# AEBS_component_FrontV1_2.net
KiCad netlist of a schematic drawn in Altium Designer
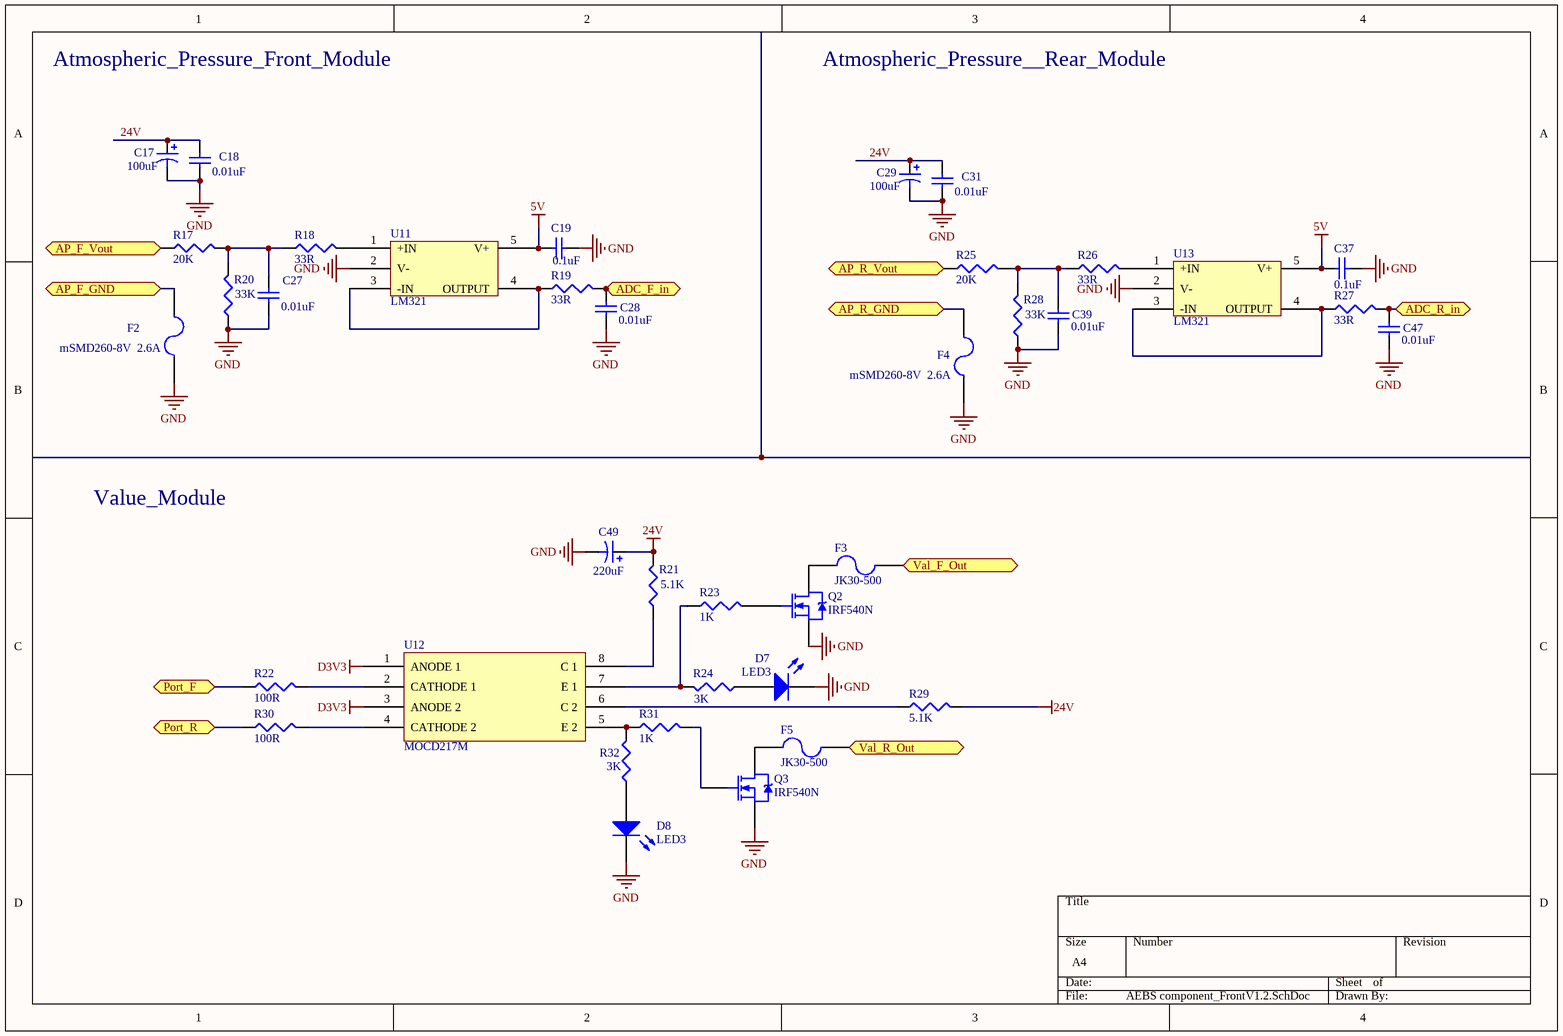
[diagram p0: AEBS component_FrontV1.2.SchDoc]

(export (version "E")
  (design (tool "Eeschema 10.0.6"))
  (components
    (comp (ref "C17")
      (value "100uF")
      (footprint "hg:CAP_POL_10*10.5")
      (description "Polarized Capacitor (Surface Mount)")
      (fields (field (name "PUBLISHER") "Altium Limited"))
      (libsource (lib "Miscellaneous Devices") (part "Cap Pol3"))
    )
    (comp (ref "C18")
      (value "0.01uF")
      (footprint "hg:0805")
      (description "Capacitor (Semiconductor SIM Model)")
      (fields (field (name "PUBLISHER") "Altium Limited"))
      (libsource (lib "Miscellaneous Devices") (part "Cap Semi"))
    )
    (comp (ref "C19")
      (value "0.1uF")
      (footprint "1608[0603]")
      (description "Capacitor (Semiconductor SIM Model)")
      (fields (field (name "PUBLISHER") "Altium Limited"))
      (libsource (lib "Miscellaneous Devices") (part "Cap Semi"))
    )
    (comp (ref "C27")
      (value "0.01uF")
      (footprint "1608[0603]")
      (description "Capacitor (Semiconductor SIM Model)")
      (fields (field (name "PUBLISHER") "Altium Limited"))
      (libsource (lib "Miscellaneous Devices") (part "Cap Semi"))
    )
    (comp (ref "C28")
      (value "0.01uF")
      (footprint "1608[0603]")
      (description "Capacitor (Semiconductor SIM Model)")
      (fields (field (name "PUBLISHER") "Altium Limited"))
      (libsource (lib "Miscellaneous Devices") (part "Cap Semi"))
    )
    (comp (ref "C29")
      (value "100uF")
      (footprint "hg:CAP_POL_10*10.5")
      (description "Polarized Capacitor (Surface Mount)")
      (fields (field (name "PUBLISHER") "Altium Limited"))
      (libsource (lib "Miscellaneous Devices") (part "Cap Pol3"))
    )
    (comp (ref "C31")
      (value "0.01uF")
      (footprint "hg:0805")
      (description "Capacitor (Semiconductor SIM Model)")
      (fields (field (name "PUBLISHER") "Altium Limited"))
      (libsource (lib "Miscellaneous Devices") (part "Cap Semi"))
    )
    (comp (ref "C37")
      (value "0.1uF")
      (footprint "1608[0603]")
      (description "Capacitor (Semiconductor SIM Model)")
      (fields (field (name "PUBLISHER") "Altium Limited"))
      (libsource (lib "Miscellaneous Devices") (part "Cap Semi"))
    )
    (comp (ref "C39")
      (value "0.01uF")
      (footprint "1608[0603]")
      (description "Capacitor (Semiconductor SIM Model)")
      (fields (field (name "PUBLISHER") "Altium Limited"))
      (libsource (lib "Miscellaneous Devices") (part "Cap Semi"))
    )
    (comp (ref "C47")
      (value "0.01uF")
      (footprint "1608[0603]")
      (description "Capacitor (Semiconductor SIM Model)")
      (fields (field (name "PUBLISHER") "Altium Limited"))
      (libsource (lib "Miscellaneous Devices") (part "Cap Semi"))
    )
    (comp (ref "C49")
      (value "220uF")
      (footprint "hg:CAP_POL_12.5*13.5")
      (description "Polarized Capacitor (Radial)")
      (fields (field (name "PUBLISHER") "Altium Limited"))
      (libsource (lib "Miscellaneous Devices") (part "Cap Pol1"))
    )
    (comp (ref "D7")
      (value "LED3")
      (footprint "hg:1206")
      (description "Typical BLUE SiC LED")
      (fields (field (name "PUBLISHER") "Altium Limited"))
      (libsource (lib "Miscellaneous Devices") (part "LED3"))
    )
    (comp (ref "D8")
      (value "LED3")
      (footprint "hg:1206")
      (description "Typical BLUE SiC LED")
      (fields (field (name "PUBLISHER") "Altium Limited"))
      (libsource (lib "Miscellaneous Devices") (part "LED3"))
    )
    (comp (ref "F2")
      (value "mSMD260-8V  2.6A")
      (footprint "1812")
      (description "Fuse")
      (fields (field (name "PUBLISHER") "Altium Limited"))
      (libsource (lib "Miscellaneous Devices") (part "Fuse 2"))
    )
    (comp (ref "F3")
      (value "JK30-500")
      (footprint "hg:JK30-500")
      (description "Fuse")
      (fields (field (name "PUBLISHER") "Altium Limited"))
      (libsource (lib "Miscellaneous Devices") (part "Fuse 2"))
    )
    (comp (ref "F4")
      (value "mSMD260-8V  2.6A")
      (footprint "1812")
      (description "Fuse")
      (fields (field (name "PUBLISHER") "Altium Limited"))
      (libsource (lib "Miscellaneous Devices") (part "Fuse 2"))
    )
    (comp (ref "F5")
      (value "JK30-500")
      (footprint "hg:JK30-500")
      (description "Fuse")
      (fields (field (name "PUBLISHER") "Altium Limited"))
      (libsource (lib "Miscellaneous Devices") (part "Fuse 2"))
    )
    (comp (ref "Q2")
      (value "IRF540N")
      (footprint "TO-220AB")
      (description "N-Channel Power MOSFET")
      (fields (field (name "PUBLISHER") "Altium Limited"))
      (libsource (lib "Miscellaneous Devices") (part "NMOS-2"))
    )
    (comp (ref "Q3")
      (value "IRF540N")
      (footprint "TO-220AB")
      (description "N-Channel Power MOSFET")
      (fields (field (name "PUBLISHER") "Altium Limited"))
      (libsource (lib "Miscellaneous Devices") (part "NMOS-2"))
    )
    (comp (ref "R17")
      (value "20K")
      (footprint "J1-0603")
      (description "Resistor")
      (fields (field (name "PUBLISHER") "Altium Limited"))
      (libsource (lib "Miscellaneous Devices") (part "Res3"))
    )
    (comp (ref "R18")
      (value "33R")
      (footprint "J1-0603")
      (description "Resistor")
      (fields (field (name "PUBLISHER") "Altium Limited"))
      (libsource (lib "Miscellaneous Devices") (part "Res3"))
    )
    (comp (ref "R19")
      (value "33R")
      (footprint "J1-0603")
      (description "Resistor")
      (fields (field (name "PUBLISHER") "Altium Limited"))
      (libsource (lib "Miscellaneous Devices") (part "Res3"))
    )
    (comp (ref "R20")
      (value "33K")
      (footprint "J1-0603")
      (description "Resistor")
      (fields (field (name "PUBLISHER") "Altium Limited"))
      (libsource (lib "Miscellaneous Devices") (part "Res3"))
    )
    (comp (ref "R21")
      (value "5.1K")
      (footprint "J1-0603")
      (description "Resistor")
      (fields (field (name "PUBLISHER") "Altium Limited"))
      (libsource (lib "Miscellaneous Devices") (part "Res3"))
    )
    (comp (ref "R22")
      (value "100R")
      (footprint "J1-0603")
      (description "Resistor")
      (fields (field (name "PUBLISHER") "Altium Limited"))
      (libsource (lib "Miscellaneous Devices") (part "Res3"))
    )
    (comp (ref "R23")
      (value "1K")
      (footprint "J1-0603")
      (description "Resistor")
      (fields (field (name "PUBLISHER") "Altium Limited"))
      (libsource (lib "Miscellaneous Devices") (part "Res3"))
    )
    (comp (ref "R24")
      (value "3K")
      (footprint "J1-0603")
      (description "Resistor")
      (fields (field (name "PUBLISHER") "Altium Limited"))
      (libsource (lib "Miscellaneous Devices") (part "Res3"))
    )
    (comp (ref "R25")
      (value "20K")
      (footprint "J1-0603")
      (description "Resistor")
      (fields (field (name "PUBLISHER") "Altium Limited"))
      (libsource (lib "Miscellaneous Devices") (part "Res3"))
    )
    (comp (ref "R26")
      (value "33R")
      (footprint "J1-0603")
      (description "Resistor")
      (fields (field (name "PUBLISHER") "Altium Limited"))
      (libsource (lib "Miscellaneous Devices") (part "Res3"))
    )
    (comp (ref "R27")
      (value "33R")
      (footprint "J1-0603")
      (description "Resistor")
      (fields (field (name "PUBLISHER") "Altium Limited"))
      (libsource (lib "Miscellaneous Devices") (part "Res3"))
    )
    (comp (ref "R28")
      (value "33K")
      (footprint "J1-0603")
      (description "Resistor")
      (fields (field (name "PUBLISHER") "Altium Limited"))
      (libsource (lib "Miscellaneous Devices") (part "Res3"))
    )
    (comp (ref "R29")
      (value "5.1K")
      (footprint "J1-0603")
      (description "Resistor")
      (fields (field (name "PUBLISHER") "Altium Limited"))
      (libsource (lib "Miscellaneous Devices") (part "Res3"))
    )
    (comp (ref "R30")
      (value "100R")
      (footprint "J1-0603")
      (description "Resistor")
      (fields (field (name "PUBLISHER") "Altium Limited"))
      (libsource (lib "Miscellaneous Devices") (part "Res3"))
    )
    (comp (ref "R31")
      (value "1K")
      (footprint "J1-0603")
      (description "Resistor")
      (fields (field (name "PUBLISHER") "Altium Limited"))
      (libsource (lib "Miscellaneous Devices") (part "Res3"))
    )
    (comp (ref "R32")
      (value "3K")
      (footprint "J1-0603")
      (description "Resistor")
      (fields (field (name "PUBLISHER") "Altium Limited"))
      (libsource (lib "Miscellaneous Devices") (part "Res3"))
    )
    (comp (ref "U11") (value "LM321") (footprint "hg:LM321") (libsource (lib "hg") (part "LM321")))
    (comp (ref "U12") (value "MOCD217M") (footprint "hg:MOCD217M") (libsource (lib "hg") (part "MOCD217M")))
    (comp (ref "U13") (value "LM321") (footprint "hg:LM321") (libsource (lib "hg") (part "LM321")))
  )
  (nets
    (net (code "1") (name "/ADC_F_in") (class "Default")
      (node (ref "C28") (pin "2") (pinfunction "2_2") (pintype "passive"))
      (node (ref "R19") (pin "2") (pinfunction "2_2") (pintype "passive"))
    )
    (net (code "2") (name "/ADC_R_in") (class "Default")
      (node (ref "C47") (pin "2") (pinfunction "2_2") (pintype "passive"))
      (node (ref "R27") (pin "2") (pinfunction "2_2") (pintype "passive"))
    )
    (net (code "3") (name "/AP_F_GND") (class "Default")
      (node (ref "F2") (pin "1") (pinfunction "1_1") (pintype "passive"))
    )
    (net (code "4") (name "/AP_F_Vout") (class "Default")
      (node (ref "R17") (pin "1") (pinfunction "1_1") (pintype "passive"))
    )
    (net (code "5") (name "/AP_R_GND") (class "Default")
      (node (ref "F4") (pin "1") (pinfunction "1_1") (pintype "passive"))
    )
    (net (code "6") (name "/AP_R_Vout") (class "Default")
      (node (ref "R25") (pin "1") (pinfunction "1_1") (pintype "passive"))
    )
    (net (code "7") (name "/Port_F") (class "Default")
      (node (ref "R22") (pin "1") (pinfunction "1_1") (pintype "passive"))
    )
    (net (code "8") (name "/Port_R") (class "Default")
      (node (ref "R30") (pin "1") (pinfunction "1_1") (pintype "passive"))
    )
    (net (code "9") (name "/Val_F_Out") (class "Default")
      (node (ref "F3") (pin "2") (pinfunction "2_2") (pintype "passive"))
    )
    (net (code "10") (name "/Val_R_Out") (class "Default")
      (node (ref "F5") (pin "2") (pinfunction "2_2") (pintype "passive"))
    )
    (net (code "11") (name "5V") (class "Default")
      (node (ref "C19") (pin "2") (pinfunction "2_2") (pintype "passive"))
      (node (ref "C37") (pin "2") (pinfunction "2_2") (pintype "passive"))
      (node (ref "U11") (pin "5") (pinfunction "V+_5") (pintype "passive"))
      (node (ref "U13") (pin "5") (pinfunction "V+_5") (pintype "passive"))
    )
    (net (code "12") (name "24V") (class "Default")
      (node (ref "C17") (pin "1") (pinfunction "1_1") (pintype "passive"))
      (node (ref "C18") (pin "1") (pinfunction "1_1") (pintype "passive"))
      (node (ref "C29") (pin "1") (pinfunction "1_1") (pintype "passive"))
      (node (ref "C31") (pin "1") (pinfunction "1_1") (pintype "passive"))
      (node (ref "C49") (pin "1") (pinfunction "1_1") (pintype "passive"))
      (node (ref "R21") (pin "2") (pinfunction "2_2") (pintype "passive"))
      (node (ref "R29") (pin "2") (pinfunction "2_2") (pintype "passive"))
    )
    (net (code "13") (name "D3V3") (class "Default")
      (node (ref "U12") (pin "1") (pinfunction "ANODE_1_1") (pintype "passive"))
      (node (ref "U12") (pin "3") (pinfunction "ANODE_2_3") (pintype "passive"))
    )
    (net (code "14") (name "GND") (class "Default")
      (node (ref "C17") (pin "2") (pinfunction "2_2") (pintype "passive"))
      (node (ref "C18") (pin "2") (pinfunction "2_2") (pintype "passive"))
      (node (ref "C19") (pin "1") (pinfunction "1_1") (pintype "passive"))
      (node (ref "C27") (pin "1") (pinfunction "1_1") (pintype "passive"))
      (node (ref "C28") (pin "1") (pinfunction "1_1") (pintype "passive"))
      (node (ref "C29") (pin "2") (pinfunction "2_2") (pintype "passive"))
      (node (ref "C31") (pin "2") (pinfunction "2_2") (pintype "passive"))
      (node (ref "C37") (pin "1") (pinfunction "1_1") (pintype "passive"))
      (node (ref "C39") (pin "1") (pinfunction "1_1") (pintype "passive"))
      (node (ref "C47") (pin "1") (pinfunction "1_1") (pintype "passive"))
      (node (ref "C49") (pin "2") (pinfunction "2_2") (pintype "passive"))
      (node (ref "D7") (pin "2") (pinfunction "K_2") (pintype "passive"))
      (node (ref "D8") (pin "2") (pinfunction "K_2") (pintype "passive"))
      (node (ref "F2") (pin "2") (pinfunction "2_2") (pintype "passive"))
      (node (ref "F4") (pin "2") (pinfunction "2_2") (pintype "passive"))
      (node (ref "Q2") (pin "3") (pinfunction "S_3") (pintype "passive"))
      (node (ref "Q3") (pin "3") (pinfunction "S_3") (pintype "passive"))
      (node (ref "R20") (pin "1") (pinfunction "1_1") (pintype "passive"))
      (node (ref "R28") (pin "1") (pinfunction "1_1") (pintype "passive"))
      (node (ref "U11") (pin "2") (pinfunction "V-_2") (pintype "passive"))
      (node (ref "U13") (pin "2") (pinfunction "V-_2") (pintype "passive"))
    )
    (net (code "15") (name "Net-(C27-Pad2)") (class "Default")
      (node (ref "C27") (pin "2") (pinfunction "2_2") (pintype "passive"))
      (node (ref "R17") (pin "2") (pinfunction "2_2") (pintype "passive"))
      (node (ref "R18") (pin "1") (pinfunction "1_1") (pintype "passive"))
      (node (ref "R20") (pin "2") (pinfunction "2_2") (pintype "passive"))
    )
    (net (code "16") (name "Net-(C39-Pad2)") (class "Default")
      (node (ref "C39") (pin "2") (pinfunction "2_2") (pintype "passive"))
      (node (ref "R25") (pin "2") (pinfunction "2_2") (pintype "passive"))
      (node (ref "R26") (pin "1") (pinfunction "1_1") (pintype "passive"))
      (node (ref "R28") (pin "2") (pinfunction "2_2") (pintype "passive"))
    )
    (net (code "17") (name "Net-(D7-A)") (class "Default")
      (node (ref "D7") (pin "1") (pinfunction "A_1") (pintype "passive"))
      (node (ref "R24") (pin "1") (pinfunction "1_1") (pintype "passive"))
    )
    (net (code "18") (name "Net-(D8-A)") (class "Default")
      (node (ref "D8") (pin "1") (pinfunction "A_1") (pintype "passive"))
      (node (ref "R32") (pin "1") (pinfunction "1_1") (pintype "passive"))
    )
    (net (code "19") (name "Net-(Q2-D)") (class "Default")
      (node (ref "F3") (pin "1") (pinfunction "1_1") (pintype "passive"))
      (node (ref "Q2") (pin "2") (pinfunction "D_2") (pintype "passive"))
    )
    (net (code "20") (name "Net-(Q2-G)") (class "Default")
      (node (ref "Q2") (pin "1") (pinfunction "G_1") (pintype "passive"))
      (node (ref "R23") (pin "2") (pinfunction "2_2") (pintype "passive"))
    )
    (net (code "21") (name "Net-(Q3-D)") (class "Default")
      (node (ref "F5") (pin "1") (pinfunction "1_1") (pintype "passive"))
      (node (ref "Q3") (pin "2") (pinfunction "D_2") (pintype "passive"))
    )
    (net (code "22") (name "Net-(Q3-G)") (class "Default")
      (node (ref "Q3") (pin "1") (pinfunction "G_1") (pintype "passive"))
      (node (ref "R31") (pin "2") (pinfunction "2_2") (pintype "passive"))
    )
    (net (code "23") (name "Net-(U11-+IN)") (class "Default")
      (node (ref "R18") (pin "2") (pinfunction "2_2") (pintype "passive"))
      (node (ref "U11") (pin "1") (pinfunction "+IN_1") (pintype "passive"))
    )
    (net (code "24") (name "Net-(U11--IN)") (class "Default")
      (node (ref "R19") (pin "1") (pinfunction "1_1") (pintype "passive"))
      (node (ref "U11") (pin "3") (pinfunction "-IN_3") (pintype "passive"))
      (node (ref "U11") (pin "4") (pinfunction "OUTPUT_4") (pintype "passive"))
    )
    (net (code "25") (name "Net-(U12-CATHODE_1)") (class "Default")
      (node (ref "R22") (pin "2") (pinfunction "2_2") (pintype "passive"))
      (node (ref "U12") (pin "2") (pinfunction "CATHODE_1_2") (pintype "passive"))
    )
    (net (code "26") (name "Net-(U12-CATHODE_2)") (class "Default")
      (node (ref "R30") (pin "2") (pinfunction "2_2") (pintype "passive"))
      (node (ref "U12") (pin "4") (pinfunction "CATHODE_2_4") (pintype "passive"))
    )
    (net (code "27") (name "Net-(U12-C_1)") (class "Default")
      (node (ref "R21") (pin "1") (pinfunction "1_1") (pintype "passive"))
      (node (ref "U12") (pin "8") (pinfunction "C_1_8") (pintype "passive"))
    )
    (net (code "28") (name "Net-(U12-C_2)") (class "Default")
      (node (ref "R29") (pin "1") (pinfunction "1_1") (pintype "passive"))
      (node (ref "U12") (pin "6") (pinfunction "C_2_6") (pintype "passive"))
    )
    (net (code "29") (name "Net-(U12-E_1)") (class "Default")
      (node (ref "R23") (pin "1") (pinfunction "1_1") (pintype "passive"))
      (node (ref "R24") (pin "2") (pinfunction "2_2") (pintype "passive"))
      (node (ref "U12") (pin "7") (pinfunction "E_1_7") (pintype "passive"))
    )
    (net (code "30") (name "Net-(U12-E_2)") (class "Default")
      (node (ref "R31") (pin "1") (pinfunction "1_1") (pintype "passive"))
      (node (ref "R32") (pin "2") (pinfunction "2_2") (pintype "passive"))
      (node (ref "U12") (pin "5") (pinfunction "E_2_5") (pintype "passive"))
    )
    (net (code "31") (name "Net-(U13-+IN)") (class "Default")
      (node (ref "R26") (pin "2") (pinfunction "2_2") (pintype "passive"))
      (node (ref "U13") (pin "1") (pinfunction "+IN_1") (pintype "passive"))
    )
    (net (code "32") (name "Net-(U13--IN)") (class "Default")
      (node (ref "R27") (pin "1") (pinfunction "1_1") (pintype "passive"))
      (node (ref "U13") (pin "3") (pinfunction "-IN_3") (pintype "passive"))
      (node (ref "U13") (pin "4") (pinfunction "OUTPUT_4") (pintype "passive"))
    )
  )
)
